# 4ButtonSwitch_Rev3_0.net
KiCad netlist of a schematic drawn in EAGLE
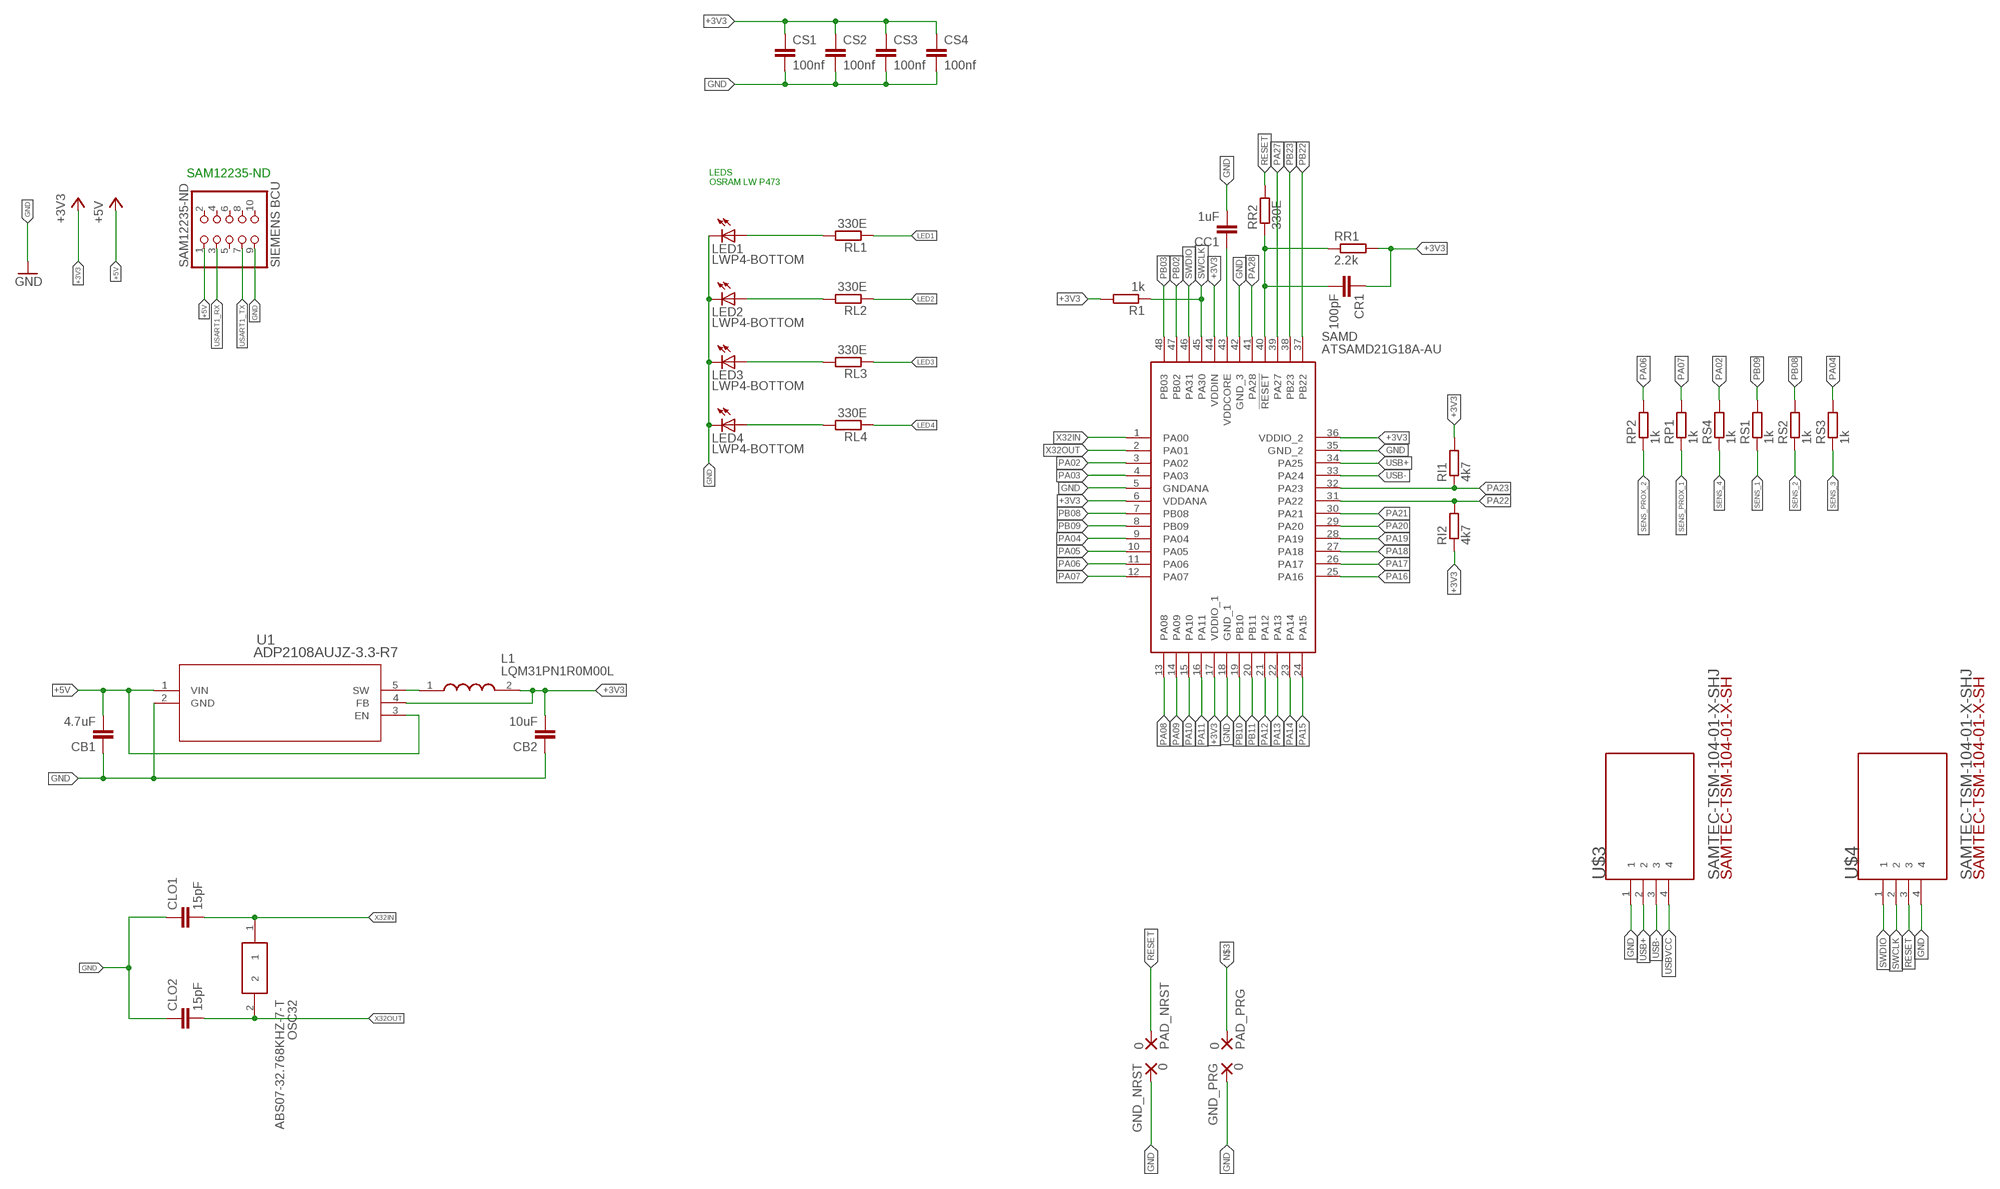
[diagram p0: schematic, sheet 1]

(export (version "E")
  (design (tool "Eeschema 10.0.6"))
  (components
    (comp (ref "CB1")
      (value "4.7uF")
      (footprint "eagle-import:C1206")
      (libsource (lib "eagle-import") (part "C-EUC1206"))
    )
    (comp (ref "CB2")
      (value "10uF")
      (footprint "eagle-import:C1206")
      (libsource (lib "eagle-import") (part "C-EUC1206"))
    )
    (comp (ref "CC1")
      (value "1uF")
      (footprint "eagle-import:C1206")
      (libsource (lib "eagle-import") (part "C-EUC1206"))
    )
    (comp (ref "CLO1")
      (value "15pF")
      (footprint "eagle-import:C1206")
      (libsource (lib "eagle-import") (part "C-EUC1206"))
    )
    (comp (ref "CLO2")
      (value "15pF")
      (footprint "eagle-import:C1206")
      (libsource (lib "eagle-import") (part "C-EUC1206"))
    )
    (comp (ref "CR1")
      (value "100pF")
      (footprint "eagle-import:C1206")
      (libsource (lib "eagle-import") (part "C-EUC1206"))
    )
    (comp (ref "CS1")
      (value "100nf")
      (footprint "eagle-import:C1206")
      (libsource (lib "eagle-import") (part "C-EUC1206"))
    )
    (comp (ref "CS2")
      (value "100nf")
      (footprint "eagle-import:C1206")
      (libsource (lib "eagle-import") (part "C-EUC1206"))
    )
    (comp (ref "CS3")
      (value "100nf")
      (footprint "eagle-import:C1206")
      (libsource (lib "eagle-import") (part "C-EUC1206"))
    )
    (comp (ref "CS4")
      (value "100nf")
      (footprint "eagle-import:C1206")
      (libsource (lib "eagle-import") (part "C-EUC1206"))
    )
    (comp (ref "GND_NRST")
      (value "0")
      (footprint "eagle-import:SMD2,54-5,08")
      (libsource (lib "eagle-import") (part "SMD5"))
    )
    (comp (ref "GND_PRG")
      (value "0")
      (footprint "eagle-import:SMD2,54-5,08")
      (libsource (lib "eagle-import") (part "SMD5"))
    )
    (comp (ref "L1")
      (value "LQM31PN1R0M00L")
      (footprint "eagle-import:INDC3216X95N")
      (fields (field (name "RS_PART_NUMBER") "1674189"))
      (libsource (lib "eagle-import") (part "LQM31PN1R0M00L"))
    )
    (comp (ref "LED1")
      (value "LWP4-BOTTOM")
      (footprint "eagle-import:P47F-BOTTOM")
      (libsource (lib "eagle-import") (part "P4-BOTTOMLW"))
    )
    (comp (ref "LED2")
      (value "LWP4-BOTTOM")
      (footprint "eagle-import:P47F-BOTTOM")
      (libsource (lib "eagle-import") (part "P4-BOTTOMLW"))
    )
    (comp (ref "LED3")
      (value "LWP4-BOTTOM")
      (footprint "eagle-import:P47F-BOTTOM")
      (libsource (lib "eagle-import") (part "P4-BOTTOMLW"))
    )
    (comp (ref "LED4")
      (value "LWP4-BOTTOM")
      (footprint "eagle-import:P47F-BOTTOM")
      (libsource (lib "eagle-import") (part "P4-BOTTOMLW"))
    )
    (comp (ref "OSC32")
      (value "ABS07-32.768KHZ-7-T")
      (footprint "eagle-import:ABS-07")
      (fields (field (name "RS_PART_NUMBER") "1712773P"))
      (libsource (lib "eagle-import") (part "ABS07-32.768KHZ-7-T"))
    )
    (comp (ref "PAD_NRST")
      (value "0")
      (footprint "eagle-import:SMD2,54-5,08")
      (libsource (lib "eagle-import") (part "SMD5"))
    )
    (comp (ref "PAD_PRG")
      (value "0")
      (footprint "eagle-import:SMD2,54-5,08")
      (libsource (lib "eagle-import") (part "SMD5"))
    )
    (comp (ref "R1")
      (value "1k")
      (footprint "eagle-import:R1206")
      (libsource (lib "eagle-import") (part "R-EU_R1206"))
    )
    (comp (ref "RI1")
      (value "4k7")
      (footprint "eagle-import:R1206")
      (libsource (lib "eagle-import") (part "R-EU_R1206"))
    )
    (comp (ref "RI2")
      (value "4k7")
      (footprint "eagle-import:R1206")
      (libsource (lib "eagle-import") (part "R-EU_R1206"))
    )
    (comp (ref "RL1")
      (value "330E")
      (footprint "eagle-import:R1206")
      (libsource (lib "eagle-import") (part "R-EU_R1206"))
    )
    (comp (ref "RL2")
      (value "330E")
      (footprint "eagle-import:R1206")
      (libsource (lib "eagle-import") (part "R-EU_R1206"))
    )
    (comp (ref "RL3")
      (value "330E")
      (footprint "eagle-import:R1206")
      (libsource (lib "eagle-import") (part "R-EU_R1206"))
    )
    (comp (ref "RL4")
      (value "330E")
      (footprint "eagle-import:R1206")
      (libsource (lib "eagle-import") (part "R-EU_R1206"))
    )
    (comp (ref "RP1")
      (value "1k")
      (footprint "eagle-import:R1206")
      (libsource (lib "eagle-import") (part "R-EU_R1206"))
    )
    (comp (ref "RP2")
      (value "1k")
      (footprint "eagle-import:R1206")
      (libsource (lib "eagle-import") (part "R-EU_R1206"))
    )
    (comp (ref "RR1")
      (value "2.2k")
      (footprint "eagle-import:R1206")
      (libsource (lib "eagle-import") (part "R-EU_R1206"))
    )
    (comp (ref "RR2")
      (value "330E")
      (footprint "eagle-import:R1206")
      (libsource (lib "eagle-import") (part "R-EU_R1206"))
    )
    (comp (ref "RS1")
      (value "1k")
      (footprint "eagle-import:R1206")
      (libsource (lib "eagle-import") (part "R-EU_R1206"))
    )
    (comp (ref "RS2")
      (value "1k")
      (footprint "eagle-import:R1206")
      (libsource (lib "eagle-import") (part "R-EU_R1206"))
    )
    (comp (ref "RS3")
      (value "1k")
      (footprint "eagle-import:R1206")
      (libsource (lib "eagle-import") (part "R-EU_R1206"))
    )
    (comp (ref "RS4")
      (value "1k")
      (footprint "eagle-import:R1206")
      (libsource (lib "eagle-import") (part "R-EU_R1206"))
    )
    (comp (ref "SAM12235-ND")
      (value "SIEMENS BCU")
      (footprint "eagle-import:2X05SMD")
      (libsource (lib "eagle-import") (part "PINHD-2X5_2.54-SMD"))
    )
    (comp (ref "SAMD")
      (value "ATSAMD21G18A-AU")
      (footprint "eagle-import:QFP50P900X900X120-48N")
      (fields (field (name "RS_PART_NUMBER") "1773799P"))
      (libsource (lib "eagle-import") (part "ATSAMD21G18A-AU"))
    )
    (comp (ref "U$3")
      (value "SAMTEC-TSM-104-01-X-SHJ")
      (footprint "eagle-import:SAMTEC-TSM-104-01-X-SH")
      (fields (field (name "MF") "Samtec") (field (name "MP") "TSM-104-01-T-SH"))
      (libsource (lib "eagle-import") (part "SAMTEC-TSM-104-01-X-SHJ"))
    )
    (comp (ref "U$4")
      (value "SAMTEC-TSM-104-01-X-SHJ")
      (footprint "eagle-import:SAMTEC-TSM-104-01-X-SH")
      (fields (field (name "MF") "Samtec") (field (name "MP") "TSM-104-01-T-SH"))
      (libsource (lib "eagle-import") (part "SAMTEC-TSM-104-01-X-SHJ"))
    )
    (comp (ref "U1")
      (value "ADP2108AUJZ-3.3-R7")
      (footprint "eagle-import:UJ_5")
      (fields (field (name "MANUFACTURER_PART_NUMBER") "ADP2108AUJZ3.3R7"))
      (libsource (lib "eagle-import") (part "ADP2108AUJZ-3.3-R7"))
    )
  )
  (nets
    (net (code "1") (name "+3V3") (class "Default")
      (node (ref "CB2") (pin "2") (pinfunction "2_2") (pintype "passive"))
      (node (ref "CR1") (pin "1") (pinfunction "1_1") (pintype "passive"))
      (node (ref "CS1") (pin "1") (pinfunction "1_1") (pintype "passive"))
      (node (ref "CS2") (pin "1") (pinfunction "1_1") (pintype "passive"))
      (node (ref "CS3") (pin "1") (pinfunction "1_1") (pintype "passive"))
      (node (ref "CS4") (pin "1") (pinfunction "1_1") (pintype "passive"))
      (node (ref "L1") (pin "2") (pinfunction "2_2") (pintype "bidirectional"))
      (node (ref "R1") (pin "2") (pinfunction "2_2") (pintype "passive"))
      (node (ref "RI1") (pin "2") (pinfunction "2_2") (pintype "passive"))
      (node (ref "RI2") (pin "1") (pinfunction "1_1") (pintype "passive"))
      (node (ref "RR1") (pin "2") (pinfunction "2_2") (pintype "passive"))
      (node (ref "SAMD") (pin "17") (pinfunction "VDDIO_1_17") (pintype "bidirectional"))
      (node (ref "SAMD") (pin "36") (pinfunction "VDDIO_2_36") (pintype "bidirectional"))
      (node (ref "SAMD") (pin "44") (pinfunction "VDDIN_44") (pintype "bidirectional"))
      (node (ref "SAMD") (pin "6") (pinfunction "VDDANA_6") (pintype "bidirectional"))
      (node (ref "U1") (pin "4") (pinfunction "FB_4") (pintype "passive"))
    )
    (net (code "2") (name "+5V") (class "Default")
      (node (ref "CB1") (pin "2") (pinfunction "2_2") (pintype "passive"))
      (node (ref "SAM12235-ND") (pin "1") (pinfunction "1_1") (pintype "passive"))
      (node (ref "U1") (pin "1") (pinfunction "VIN_1") (pintype "passive"))
      (node (ref "U1") (pin "3") (pinfunction "EN_3") (pintype "passive"))
    )
    (net (code "3") (name "GND") (class "Default")
      (node (ref "CB1") (pin "1") (pinfunction "1_1") (pintype "passive"))
      (node (ref "CB2") (pin "1") (pinfunction "1_1") (pintype "passive"))
      (node (ref "CC1") (pin "2") (pinfunction "2_2") (pintype "passive"))
      (node (ref "CLO1") (pin "1") (pinfunction "1_1") (pintype "passive"))
      (node (ref "CLO2") (pin "1") (pinfunction "1_1") (pintype "passive"))
      (node (ref "CS1") (pin "2") (pinfunction "2_2") (pintype "passive"))
      (node (ref "CS2") (pin "2") (pinfunction "2_2") (pintype "passive"))
      (node (ref "CS3") (pin "2") (pinfunction "2_2") (pintype "passive"))
      (node (ref "CS4") (pin "2") (pinfunction "2_2") (pintype "passive"))
      (node (ref "GND_NRST") (pin "1") (pinfunction "P_1") (pintype "passive"))
      (node (ref "GND_PRG") (pin "1") (pinfunction "P_1") (pintype "passive"))
      (node (ref "LED1") (pin "C") (pinfunction "C_C") (pintype "passive"))
      (node (ref "LED2") (pin "C") (pinfunction "C_C") (pintype "passive"))
      (node (ref "LED3") (pin "C") (pinfunction "C_C") (pintype "passive"))
      (node (ref "LED4") (pin "C") (pinfunction "C_C") (pintype "passive"))
      (node (ref "SAM12235-ND") (pin "9") (pinfunction "9_9") (pintype "passive"))
      (node (ref "SAMD") (pin "18") (pinfunction "GND_1_18") (pintype "bidirectional"))
      (node (ref "SAMD") (pin "35") (pinfunction "GND_2_35") (pintype "bidirectional"))
      (node (ref "SAMD") (pin "42") (pinfunction "GND_3_42") (pintype "bidirectional"))
      (node (ref "SAMD") (pin "5") (pinfunction "GNDANA_5") (pintype "bidirectional"))
      (node (ref "U$3") (pin "1") (pinfunction "1_1") (pintype "bidirectional"))
      (node (ref "U$4") (pin "4") (pinfunction "4_4") (pintype "bidirectional"))
      (node (ref "U1") (pin "2") (pinfunction "GND_2") (pintype "passive"))
    )
    (net (code "4") (name "LED1") (class "Default")
      (node (ref "RL1") (pin "1") (pinfunction "1_1") (pintype "passive"))
    )
    (net (code "5") (name "LED2") (class "Default")
      (node (ref "RL2") (pin "1") (pinfunction "1_1") (pintype "passive"))
    )
    (net (code "6") (name "LED3") (class "Default")
      (node (ref "RL3") (pin "1") (pinfunction "1_1") (pintype "passive"))
    )
    (net (code "7") (name "LED4") (class "Default")
      (node (ref "RL4") (pin "1") (pinfunction "1_1") (pintype "passive"))
    )
    (net (code "8") (name "N$3") (class "Default")
      (node (ref "PAD_PRG") (pin "1") (pinfunction "P_1") (pintype "passive"))
    )
    (net (code "9") (name "Net-(LED1-PadA)") (class "Default")
      (node (ref "LED1") (pin "A") (pinfunction "A_A") (pintype "passive"))
      (node (ref "RL1") (pin "2") (pinfunction "2_2") (pintype "passive"))
    )
    (net (code "10") (name "Net-(LED2-PadA)") (class "Default")
      (node (ref "LED2") (pin "A") (pinfunction "A_A") (pintype "passive"))
      (node (ref "RL2") (pin "2") (pinfunction "2_2") (pintype "passive"))
    )
    (net (code "11") (name "Net-(LED3-PadA)") (class "Default")
      (node (ref "LED3") (pin "A") (pinfunction "A_A") (pintype "passive"))
      (node (ref "RL3") (pin "2") (pinfunction "2_2") (pintype "passive"))
    )
    (net (code "12") (name "Net-(LED4-PadA)") (class "Default")
      (node (ref "LED4") (pin "A") (pinfunction "A_A") (pintype "passive"))
      (node (ref "RL4") (pin "2") (pinfunction "2_2") (pintype "passive"))
    )
    (net (code "13") (name "Net-(SAMD-VDDCORE)") (class "Default")
      (node (ref "CC1") (pin "1") (pinfunction "1_1") (pintype "passive"))
      (node (ref "SAMD") (pin "43") (pinfunction "VDDCORE_43") (pintype "bidirectional"))
    )
    (net (code "14") (name "Net-(SAMD-~{RESET})") (class "Default")
      (node (ref "CR1") (pin "2") (pinfunction "2_2") (pintype "passive"))
      (node (ref "RR1") (pin "1") (pinfunction "1_1") (pintype "passive"))
      (node (ref "RR2") (pin "1") (pinfunction "1_1") (pintype "passive"))
      (node (ref "SAMD") (pin "40") (pinfunction "~{RESET}_40") (pintype "bidirectional"))
    )
    (net (code "15") (name "Net-(U1-SW)") (class "Default")
      (node (ref "L1") (pin "1") (pinfunction "1_1") (pintype "bidirectional"))
      (node (ref "U1") (pin "5") (pinfunction "SW_5") (pintype "passive"))
    )
    (net (code "16") (name "PA02") (class "Default")
      (node (ref "RS4") (pin "2") (pinfunction "2_2") (pintype "passive"))
      (node (ref "SAMD") (pin "3") (pinfunction "PA02_3") (pintype "bidirectional"))
    )
    (net (code "17") (name "PA03") (class "Default")
      (node (ref "SAMD") (pin "4") (pinfunction "PA03_4") (pintype "bidirectional"))
    )
    (net (code "18") (name "PA04") (class "Default")
      (node (ref "RS3") (pin "2") (pinfunction "2_2") (pintype "passive"))
      (node (ref "SAMD") (pin "9") (pinfunction "PA04_9") (pintype "bidirectional"))
    )
    (net (code "19") (name "PA05") (class "Default")
      (node (ref "SAMD") (pin "10") (pinfunction "PA05_10") (pintype "bidirectional"))
    )
    (net (code "20") (name "PA06") (class "Default")
      (node (ref "RP2") (pin "2") (pinfunction "2_2") (pintype "passive"))
      (node (ref "SAMD") (pin "11") (pinfunction "PA06_11") (pintype "bidirectional"))
    )
    (net (code "21") (name "PA07") (class "Default")
      (node (ref "RP1") (pin "2") (pinfunction "2_2") (pintype "passive"))
      (node (ref "SAMD") (pin "12") (pinfunction "PA07_12") (pintype "bidirectional"))
    )
    (net (code "22") (name "PA08") (class "Default")
      (node (ref "SAMD") (pin "13") (pinfunction "PA08_13") (pintype "bidirectional"))
    )
    (net (code "23") (name "PA09") (class "Default")
      (node (ref "SAMD") (pin "14") (pinfunction "PA09_14") (pintype "bidirectional"))
    )
    (net (code "24") (name "PA10") (class "Default")
      (node (ref "SAMD") (pin "15") (pinfunction "PA10_15") (pintype "bidirectional"))
    )
    (net (code "25") (name "PA11") (class "Default")
      (node (ref "SAMD") (pin "16") (pinfunction "PA11_16") (pintype "bidirectional"))
    )
    (net (code "26") (name "PA12") (class "Default")
      (node (ref "SAMD") (pin "21") (pinfunction "PA12_21") (pintype "bidirectional"))
    )
    (net (code "27") (name "PA13") (class "Default")
      (node (ref "SAMD") (pin "22") (pinfunction "PA13_22") (pintype "bidirectional"))
    )
    (net (code "28") (name "PA14") (class "Default")
      (node (ref "SAMD") (pin "23") (pinfunction "PA14_23") (pintype "bidirectional"))
    )
    (net (code "29") (name "PA15") (class "Default")
      (node (ref "SAMD") (pin "24") (pinfunction "PA15_24") (pintype "bidirectional"))
    )
    (net (code "30") (name "PA16") (class "Default")
      (node (ref "SAMD") (pin "25") (pinfunction "PA16_25") (pintype "bidirectional"))
    )
    (net (code "31") (name "PA17") (class "Default")
      (node (ref "SAMD") (pin "26") (pinfunction "PA17_26") (pintype "bidirectional"))
    )
    (net (code "32") (name "PA18") (class "Default")
      (node (ref "SAMD") (pin "27") (pinfunction "PA18_27") (pintype "bidirectional"))
    )
    (net (code "33") (name "PA19") (class "Default")
      (node (ref "SAMD") (pin "28") (pinfunction "PA19_28") (pintype "bidirectional"))
    )
    (net (code "34") (name "PA20") (class "Default")
      (node (ref "SAMD") (pin "29") (pinfunction "PA20_29") (pintype "bidirectional"))
    )
    (net (code "35") (name "PA21") (class "Default")
      (node (ref "SAMD") (pin "30") (pinfunction "PA21_30") (pintype "bidirectional"))
    )
    (net (code "36") (name "PA22") (class "Default")
      (node (ref "RI2") (pin "2") (pinfunction "2_2") (pintype "passive"))
      (node (ref "SAMD") (pin "31") (pinfunction "PA22_31") (pintype "bidirectional"))
    )
    (net (code "37") (name "PA23") (class "Default")
      (node (ref "RI1") (pin "1") (pinfunction "1_1") (pintype "passive"))
      (node (ref "SAMD") (pin "32") (pinfunction "PA23_32") (pintype "bidirectional"))
    )
    (net (code "38") (name "PA27") (class "Default")
      (node (ref "SAMD") (pin "39") (pinfunction "PA27_39") (pintype "bidirectional"))
    )
    (net (code "39") (name "PA28") (class "Default")
      (node (ref "SAMD") (pin "41") (pinfunction "PA28_41") (pintype "bidirectional"))
    )
    (net (code "40") (name "PB02") (class "Default")
      (node (ref "SAMD") (pin "47") (pinfunction "PB02_47") (pintype "bidirectional"))
    )
    (net (code "41") (name "PB03") (class "Default")
      (node (ref "SAMD") (pin "48") (pinfunction "PB03_48") (pintype "bidirectional"))
    )
    (net (code "42") (name "PB08") (class "Default")
      (node (ref "RS2") (pin "2") (pinfunction "2_2") (pintype "passive"))
      (node (ref "SAMD") (pin "7") (pinfunction "PB08_7") (pintype "bidirectional"))
    )
    (net (code "43") (name "PB09") (class "Default")
      (node (ref "RS1") (pin "2") (pinfunction "2_2") (pintype "passive"))
      (node (ref "SAMD") (pin "8") (pinfunction "PB09_8") (pintype "bidirectional"))
    )
    (net (code "44") (name "PB10") (class "Default")
      (node (ref "SAMD") (pin "19") (pinfunction "PB10_19") (pintype "bidirectional"))
    )
    (net (code "45") (name "PB11") (class "Default")
      (node (ref "SAMD") (pin "20") (pinfunction "PB11_20") (pintype "bidirectional"))
    )
    (net (code "46") (name "PB22") (class "Default")
      (node (ref "SAMD") (pin "37") (pinfunction "PB22_37") (pintype "bidirectional"))
    )
    (net (code "47") (name "PB23") (class "Default")
      (node (ref "SAMD") (pin "38") (pinfunction "PB23_38") (pintype "bidirectional"))
    )
    (net (code "48") (name "RESET") (class "Default")
      (node (ref "PAD_NRST") (pin "1") (pinfunction "P_1") (pintype "passive"))
      (node (ref "RR2") (pin "2") (pinfunction "2_2") (pintype "passive"))
      (node (ref "U$4") (pin "3") (pinfunction "3_3") (pintype "bidirectional"))
    )
    (net (code "49") (name "SENS_1") (class "Default")
      (node (ref "RS1") (pin "1") (pinfunction "1_1") (pintype "passive"))
    )
    (net (code "50") (name "SENS_2") (class "Default")
      (node (ref "RS2") (pin "1") (pinfunction "1_1") (pintype "passive"))
    )
    (net (code "51") (name "SENS_3") (class "Default")
      (node (ref "RS3") (pin "1") (pinfunction "1_1") (pintype "passive"))
    )
    (net (code "52") (name "SENS_4") (class "Default")
      (node (ref "RS4") (pin "1") (pinfunction "1_1") (pintype "passive"))
    )
    (net (code "53") (name "SENS_PROX_1") (class "Default")
      (node (ref "RP1") (pin "1") (pinfunction "1_1") (pintype "passive"))
    )
    (net (code "54") (name "SENS_PROX_2") (class "Default")
      (node (ref "RP2") (pin "1") (pinfunction "1_1") (pintype "passive"))
    )
    (net (code "55") (name "SWCLK") (class "Default")
      (node (ref "R1") (pin "1") (pinfunction "1_1") (pintype "passive"))
      (node (ref "SAMD") (pin "45") (pinfunction "PA30_45") (pintype "bidirectional"))
      (node (ref "U$4") (pin "2") (pinfunction "2_2") (pintype "bidirectional"))
    )
    (net (code "56") (name "SWDIO") (class "Default")
      (node (ref "SAMD") (pin "46") (pinfunction "PA31_46") (pintype "bidirectional"))
      (node (ref "U$4") (pin "1") (pinfunction "1_1") (pintype "bidirectional"))
    )
    (net (code "57") (name "USART1_RX") (class "Default")
      (node (ref "SAM12235-ND") (pin "3") (pinfunction "3_3") (pintype "passive"))
    )
    (net (code "58") (name "USART1_TX") (class "Default")
      (node (ref "SAM12235-ND") (pin "7") (pinfunction "7_7") (pintype "passive"))
    )
    (net (code "59") (name "USB+") (class "Default")
      (node (ref "SAMD") (pin "34") (pinfunction "PA25_34") (pintype "bidirectional"))
      (node (ref "U$3") (pin "2") (pinfunction "2_2") (pintype "bidirectional"))
    )
    (net (code "60") (name "USB-") (class "Default")
      (node (ref "SAMD") (pin "33") (pinfunction "PA24_33") (pintype "bidirectional"))
      (node (ref "U$3") (pin "3") (pinfunction "3_3") (pintype "bidirectional"))
    )
    (net (code "61") (name "USBVCC") (class "Default")
      (node (ref "U$3") (pin "4") (pinfunction "4_4") (pintype "bidirectional"))
    )
    (net (code "62") (name "X32IN") (class "Default")
      (node (ref "CLO1") (pin "2") (pinfunction "2_2") (pintype "passive"))
      (node (ref "OSC32") (pin "1") (pinfunction "1_1") (pintype "bidirectional"))
      (node (ref "SAMD") (pin "1") (pinfunction "PA00_1") (pintype "bidirectional"))
    )
    (net (code "63") (name "X32OUT") (class "Default")
      (node (ref "CLO2") (pin "2") (pinfunction "2_2") (pintype "passive"))
      (node (ref "OSC32") (pin "2") (pinfunction "2_2") (pintype "bidirectional"))
      (node (ref "SAMD") (pin "2") (pinfunction "PA01_2") (pintype "bidirectional"))
    )
    (net (code "64") (name "unconnected-(SAM12235-ND-Pad2)") (class "Default")
      (node (ref "SAM12235-ND") (pin "2") (pinfunction "2_2") (pintype "passive"))
    )
    (net (code "65") (name "unconnected-(SAM12235-ND-Pad4)") (class "Default")
      (node (ref "SAM12235-ND") (pin "4") (pinfunction "4_4") (pintype "passive"))
    )
    (net (code "66") (name "unconnected-(SAM12235-ND-Pad5)") (class "Default")
      (node (ref "SAM12235-ND") (pin "5") (pinfunction "5_5") (pintype "passive"))
    )
    (net (code "67") (name "unconnected-(SAM12235-ND-Pad6)") (class "Default")
      (node (ref "SAM12235-ND") (pin "6") (pinfunction "6_6") (pintype "passive"))
    )
    (net (code "68") (name "unconnected-(SAM12235-ND-Pad8)") (class "Default")
      (node (ref "SAM12235-ND") (pin "8") (pinfunction "8_8") (pintype "passive"))
    )
    (net (code "69") (name "unconnected-(SAM12235-ND-Pad10)") (class "Default")
      (node (ref "SAM12235-ND") (pin "10") (pinfunction "10_10") (pintype "passive"))
    )
  )
)
